# Flaps__2023-07-31.net
KiCad netlist of a schematic drawn in Altium Designer
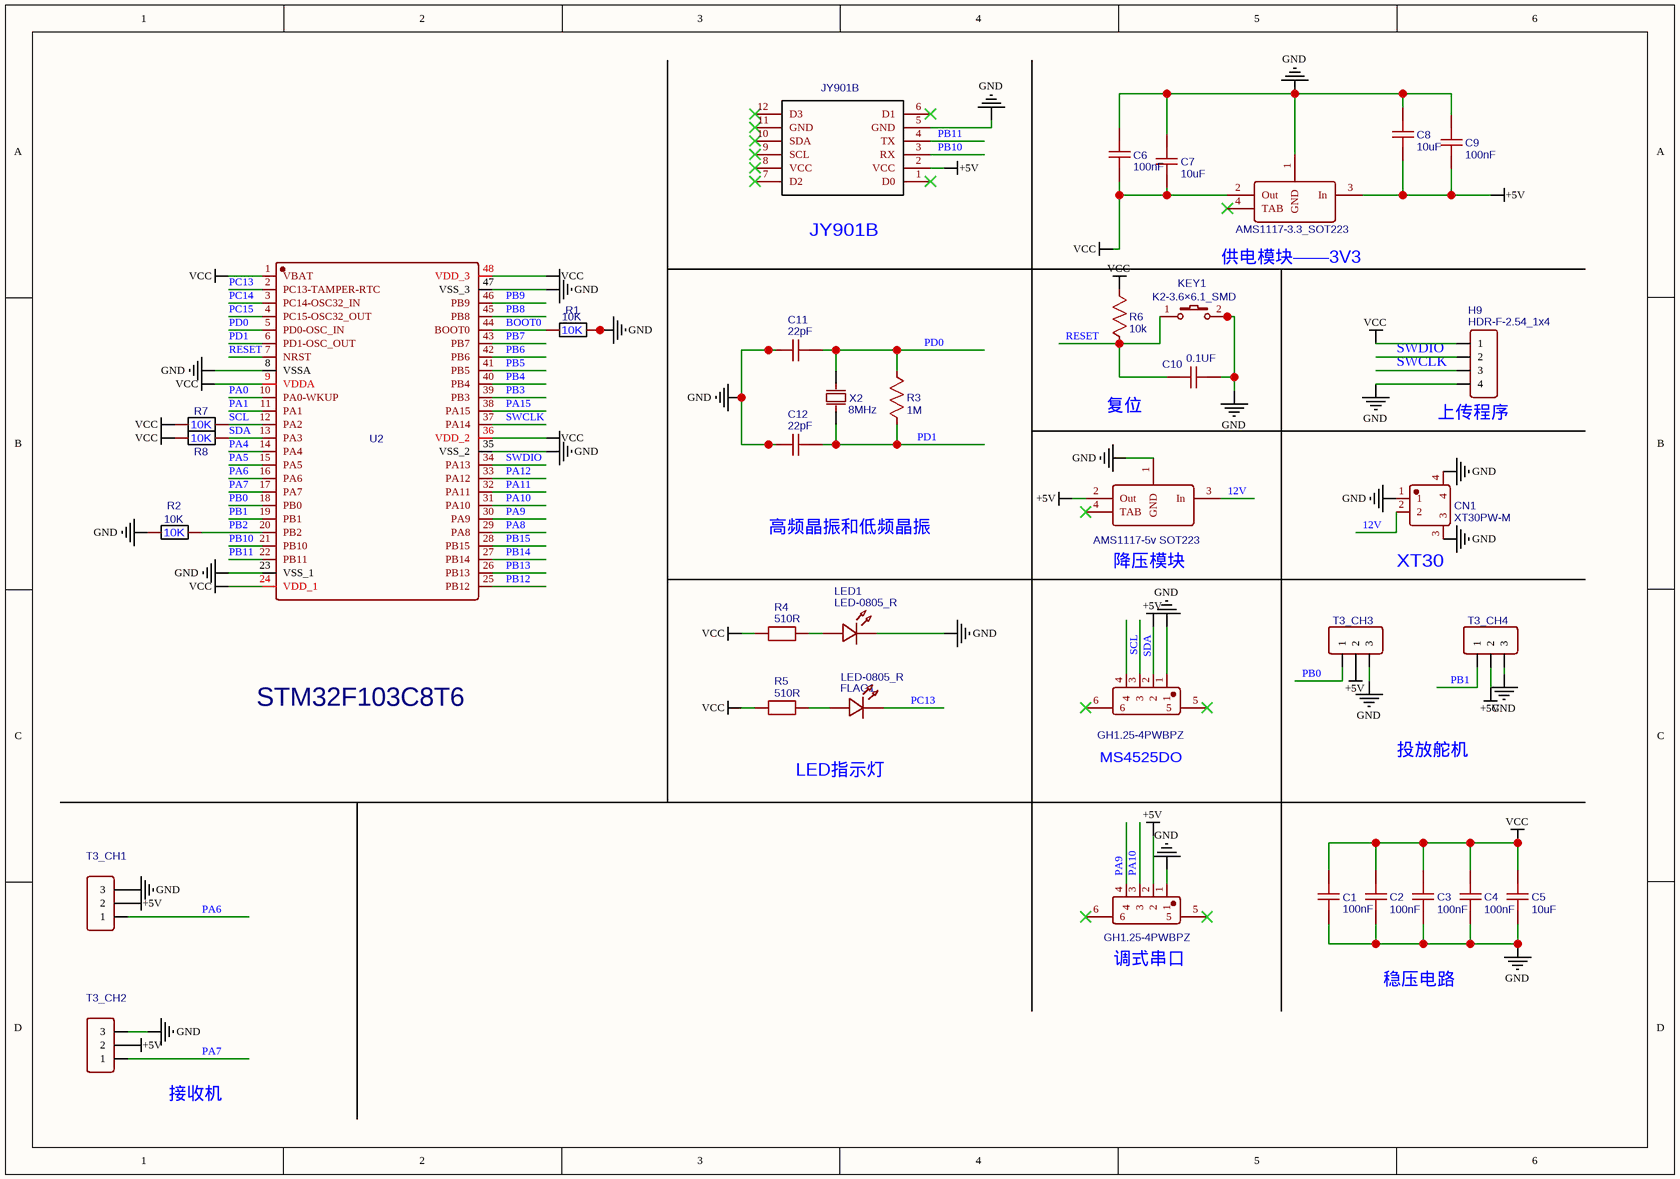
[diagram p0: Flaps第三版_2023-07-31.schdoc]

(export (version "E")
  (design (tool "Eeschema 10.0.6"))
  (components
    (comp (ref "C1")
      (value "100nF")
      (fields (field (name "CONTRIBUTOR") "LCEDA_Lib"))
      (libsource (lib "altium-import") (part "root_1_100nF_"))
    )
    (comp (ref "C2")
      (value "100nF")
      (fields (field (name "CONTRIBUTOR") "LCEDA_Lib"))
      (libsource (lib "altium-import") (part "root_1_100nF_"))
    )
    (comp (ref "C3")
      (value "100nF")
      (fields (field (name "CONTRIBUTOR") "LCEDA_Lib"))
      (libsource (lib "altium-import") (part "root_1_100nF_"))
    )
    (comp (ref "C4")
      (value "100nF")
      (fields (field (name "CONTRIBUTOR") "LCEDA_Lib"))
      (libsource (lib "altium-import") (part "root_1_100nF_"))
    )
    (comp (ref "C5")
      (value "10uF")
      (fields (field (name "CONTRIBUTOR") "LCEDA_Lib"))
      (libsource (lib "altium-import") (part "root_1_10uF_"))
    )
    (comp (ref "C6")
      (value "100nF")
      (fields (field (name "MANUFACTURER") "SAMSUNG") (field (name "MANUFACTURER PART") "CL10B104KC8NNNC"))
      (libsource (lib "altium-import") (part "root_3_100nF_"))
    )
    (comp (ref "C7")
      (value "10uF")
      (fields
        (field (name "MANUFACTURER") "Taiyo Yuden")
        (field (name "MANUFACTURER PART") "EMK316AB7106KL-T")
        (field (name "CONTRIBUTOR") "LCSC")
      )
      (libsource (lib "altium-import") (part "root_2_10uF_"))
    )
    (comp (ref "C8")
      (value "10uF")
      (fields
        (field (name "MANUFACTURER") "Taiyo Yuden")
        (field (name "MANUFACTURER PART") "EMK316AB7106KL-T")
        (field (name "CONTRIBUTOR") "LCSC")
      )
      (libsource (lib "altium-import") (part "root_2_10uF_"))
    )
    (comp (ref "C9")
      (value "100nF")
      (fields (field (name "MANUFACTURER") "SAMSUNG") (field (name "MANUFACTURER PART") "CL10B104KC8NNNC"))
      (libsource (lib "altium-import") (part "root_3_100nF_"))
    )
    (comp (ref "C10")
      (value "0.1UF")
      (fields (field (name "CONTRIBUTOR") "LCEDA_Lib"))
      (libsource (lib "altium-import") (part "root_0_0.1UF_"))
    )
    (comp (ref "C11")
      (value "22pF")
      (fields (field (name "CONTRIBUTOR") "LCEDA_Lib"))
      (libsource (lib "altium-import") (part "root_0_22pF_"))
    )
    (comp (ref "C12")
      (value "22pF")
      (fields (field (name "CONTRIBUTOR") "LCEDA_Lib"))
      (libsource (lib "altium-import") (part "root_0_22pF_"))
    )
    (comp (ref "CN1")
      (value "XT30PW-M")
      (fields (field (name "MANUFACTURER") "Changzhou Amass Elec") (field (name "CONTRIBUTOR") "LCSC"))
      (libsource (lib "altium-import") (part "root_0_XT30PW-M_"))
    )
    (comp (ref "FLAG1")
      (value "LED-0805_R")
      (fields
        (field (name "MANUFACTURER") "EVERLIGHT(台湾亿光)")
        (field (name "MANUFACTURER PART") "17-21SURC/S530-A3/TR8")
        (field (name "CONTRIBUTOR") "LCEDA_Lib")
      )
      (libsource (lib "altium-import") (part "root_0_LED-0805_R_"))
    )
    (comp (ref "H9")
      (value "HDR-F-2.54_1x4")
      (fields (field (name "CONTRIBUTOR") "LCEDA_Lib"))
      (libsource (lib "altium-import") (part "root_0_HDR-F-2.54_1x4_"))
    )
    (comp (ref "KEY1")
      (value "K2-3.6×6.1_SMD")
      (fields (field (name "MANUFACTURER PART") "K2-1107ST-A4SW-06") (field (name "CONTRIBUTOR") "LCEDA_Lib"))
      (libsource (lib "altium-import") (part "root_0_K2-3.6×6.1_SMD_"))
    )
    (comp (ref "LED1")
      (value "LED-0805_R")
      (fields
        (field (name "MANUFACTURER") "EVERLIGHT(台湾亿光)")
        (field (name "MANUFACTURER PART") "17-21SURC/S530-A3/TR8")
        (field (name "CONTRIBUTOR") "LCEDA_Lib")
      )
      (libsource (lib "altium-import") (part "root_0_LED-0805_R_"))
    )
    (comp (ref "R1")
      (value "10K")
      (fields (field (name "CONTRIBUTOR") "caocunzhangxiaobai"))
      (libsource (lib "altium-import") (part "root_0_10K_"))
    )
    (comp (ref "R2")
      (value "10K")
      (fields (field (name "CONTRIBUTOR") "caocunzhangxiaobai"))
      (libsource (lib "altium-import") (part "root_0_10K_"))
    )
    (comp (ref "R3")
      (value "1M")
      (fields (field (name "CONTRIBUTOR") "LCEDA_Lib"))
      (libsource (lib "altium-import") (part "root_1_1M_"))
    )
    (comp (ref "R4")
      (value "510R")
      (fields (field (name "CONTRIBUTOR") "LCEDA_Lib"))
      (libsource (lib "altium-import") (part "root_0_510R_"))
    )
    (comp (ref "R5")
      (value "510R")
      (fields (field (name "CONTRIBUTOR") "LCEDA_Lib"))
      (libsource (lib "altium-import") (part "root_0_510R_"))
    )
    (comp (ref "R6")
      (value "10k")
      (fields (field (name "CONTRIBUTOR") "LCEDA_Lib"))
      (libsource (lib "altium-import") (part "root_1_10k_"))
    )
    (comp (ref "R7")
      (value "10K")
      (fields (field (name "CONTRIBUTOR") "caocunzhangxiaobai"))
      (libsource (lib "altium-import") (part "root_0_10K_"))
    )
    (comp (ref "R8")
      (value "10K")
      (fields (field (name "CONTRIBUTOR") "caocunzhangxiaobai"))
      (libsource (lib "altium-import") (part "root_0_10K_"))
    )
    (comp (ref "T3_CH1")
      (value "HDR-F-2.54_1x3")
      (fields (field (name "CONTRIBUTOR") "LCEDA_Lib"))
      (libsource (lib "altium-import") (part "root_2_HDR-F-2.54_1x3_"))
    )
    (comp (ref "T3_CH2")
      (value "HDR-F-2.54_1x3")
      (fields (field (name "CONTRIBUTOR") "LCEDA_Lib"))
      (libsource (lib "altium-import") (part "root_2_HDR-F-2.54_1x3_"))
    )
    (comp (ref "T3_CH3")
      (value "HDR-F-2.54_1x3")
      (fields (field (name "CONTRIBUTOR") "LCEDA_Lib"))
      (libsource (lib "altium-import") (part "root_1_HDR-F-2.54_1x3_"))
    )
    (comp (ref "T3_CH4")
      (value "HDR-F-2.54_1x3")
      (fields (field (name "CONTRIBUTOR") "LCEDA_Lib"))
      (libsource (lib "altium-import") (part "root_1_HDR-F-2.54_1x3_"))
    )
    (comp (ref "U1")
      (value "AMS1117-3.3_SOT223")
      (fields
        (field (name "MANUFACTURER") "SK")
        (field (name "MANUFACTURER PART") "AMS1117-3.3")
        (field (name "CONTRIBUTOR") "LCSC")
      )
      (libsource (lib "altium-import") (part "root_2_AMS1117-3.3_SOT223_"))
    )
    (comp (ref "U2")
      (value "STM32F103C8T6")
      (fields (field (name "MANUFACTURER") "STMicroelectronics"))
      (libsource (lib "altium-import") (part "root_0_STM32F103C8T6_"))
    )
    (comp (ref "U3")
      (value "AMS1117-5v SOT223")
      (fields
        (field (name "MANUFACTURER") "SK")
        (field (name "MANUFACTURER PART") "AMS1117-3.3")
        (field (name "CONTRIBUTOR") "LCSC")
      )
      (libsource (lib "altium-import") (part "root_2_AMS1117-5v SOT223_"))
    )
    (comp (ref "U4")
      (value "GH1.25-4PWBPZ")
      (fields (field (name "MANUFACTURER") "BOOMELE(博穆精密)") (field (name "CONTRIBUTOR") "LCSC"))
      (libsource (lib "altium-import") (part "root_3_GH1.25-4PWBPZ_"))
    )
    (comp (ref "U5")
      (value "GH1.25-4PWBPZ")
      (fields (field (name "MANUFACTURER") "BOOMELE(博穆精密)") (field (name "CONTRIBUTOR") "LCSC"))
      (libsource (lib "altium-import") (part "root_3_GH1.25-4PWBPZ_"))
    )
    (comp (ref "U9")
      (value "JY901B")
      (fields (field (name "CONTRIBUTOR") "230W"))
      (libsource (lib "altium-import") (part "root_2_JY901B_"))
    )
    (comp (ref "X2")
      (value "8MHz")
      (fields (field (name "MANUFACTURER") "HOSONIC") (field (name "MANUFACTURER PART") "ESB8.00000F20E22"))
      (libsource (lib "altium-import") (part "root_1_8MHz_"))
    )
  )
  (nets
    (net (code "1") (name "+5V") (class "Default")
      (node (ref "C8") (pin "2") (pinfunction "2_2") (pintype "passive"))
      (node (ref "C9") (pin "2") (pinfunction "2_2") (pintype "passive"))
      (node (ref "T3_CH1") (pin "2") (pinfunction "2_2") (pintype "passive"))
      (node (ref "T3_CH2") (pin "2") (pinfunction "2_2") (pintype "passive"))
      (node (ref "T3_CH3") (pin "2") (pinfunction "2_2") (pintype "passive"))
      (node (ref "T3_CH4") (pin "2") (pinfunction "2_2") (pintype "passive"))
      (node (ref "U1") (pin "3") (pinfunction "In_3") (pintype "passive"))
      (node (ref "U3") (pin "2") (pinfunction "Out_2") (pintype "passive"))
      (node (ref "U4") (pin "2") (pinfunction "2_2") (pintype "passive"))
      (node (ref "U5") (pin "2") (pinfunction "2_2") (pintype "passive"))
      (node (ref "U9") (pin "2") (pinfunction "VCC_2") (pintype "passive"))
    )
    (net (code "2") (name "/12V") (class "Default")
      (node (ref "CN1") (pin "2") (pinfunction "2_2") (pintype "passive"))
      (node (ref "U3") (pin "3") (pinfunction "In_3") (pintype "passive"))
    )
    (net (code "3") (name "/BOOT0") (class "Default")
      (node (ref "R1") (pin "1") (pinfunction "1_1") (pintype "passive"))
      (node (ref "U2") (pin "44") (pinfunction "BOOT0_44") (pintype "passive"))
    )
    (net (code "4") (name "/PA0") (class "Default")
      (node (ref "U2") (pin "10") (pinfunction "PA0-WKUP_10") (pintype "passive"))
    )
    (net (code "5") (name "/PA1") (class "Default")
      (node (ref "U2") (pin "11") (pinfunction "PA1_11") (pintype "passive"))
    )
    (net (code "6") (name "/PA4") (class "Default")
      (node (ref "U2") (pin "14") (pinfunction "PA4_14") (pintype "passive"))
    )
    (net (code "7") (name "/PA5") (class "Default")
      (node (ref "U2") (pin "15") (pinfunction "PA5_15") (pintype "passive"))
    )
    (net (code "8") (name "/PA6") (class "Default")
      (node (ref "T3_CH1") (pin "1") (pinfunction "1_1") (pintype "passive"))
      (node (ref "U2") (pin "16") (pinfunction "PA6_16") (pintype "passive"))
    )
    (net (code "9") (name "/PA7") (class "Default")
      (node (ref "T3_CH2") (pin "1") (pinfunction "1_1") (pintype "passive"))
      (node (ref "U2") (pin "17") (pinfunction "PA7_17") (pintype "passive"))
    )
    (net (code "10") (name "/PA8") (class "Default")
      (node (ref "U2") (pin "29") (pinfunction "PA8_29") (pintype "passive"))
    )
    (net (code "11") (name "/PA9") (class "Default")
      (node (ref "U2") (pin "30") (pinfunction "PA9_30") (pintype "passive"))
      (node (ref "U5") (pin "4") (pinfunction "4_4") (pintype "passive"))
    )
    (net (code "12") (name "/PA10") (class "Default")
      (node (ref "U2") (pin "31") (pinfunction "PA10_31") (pintype "passive"))
      (node (ref "U5") (pin "3") (pinfunction "3_3") (pintype "passive"))
    )
    (net (code "13") (name "/PA11") (class "Default")
      (node (ref "U2") (pin "32") (pinfunction "PA11_32") (pintype "passive"))
    )
    (net (code "14") (name "/PA12") (class "Default")
      (node (ref "U2") (pin "33") (pinfunction "PA12_33") (pintype "passive"))
    )
    (net (code "15") (name "/PA15") (class "Default")
      (node (ref "U2") (pin "38") (pinfunction "PA15_38") (pintype "passive"))
    )
    (net (code "16") (name "/PB0") (class "Default")
      (node (ref "T3_CH3") (pin "1") (pinfunction "1_1") (pintype "passive"))
      (node (ref "U2") (pin "18") (pinfunction "PB0_18") (pintype "passive"))
    )
    (net (code "17") (name "/PB1") (class "Default")
      (node (ref "T3_CH4") (pin "1") (pinfunction "1_1") (pintype "passive"))
      (node (ref "U2") (pin "19") (pinfunction "PB1_19") (pintype "passive"))
    )
    (net (code "18") (name "/PB2") (class "Default")
      (node (ref "R2") (pin "2") (pinfunction "2_2") (pintype "passive"))
      (node (ref "U2") (pin "20") (pinfunction "PB2_20") (pintype "passive"))
    )
    (net (code "19") (name "/PB3") (class "Default")
      (node (ref "U2") (pin "39") (pinfunction "PB3_39") (pintype "passive"))
    )
    (net (code "20") (name "/PB4") (class "Default")
      (node (ref "U2") (pin "40") (pinfunction "PB4_40") (pintype "passive"))
    )
    (net (code "21") (name "/PB5") (class "Default")
      (node (ref "U2") (pin "41") (pinfunction "PB5_41") (pintype "passive"))
    )
    (net (code "22") (name "/PB6") (class "Default")
      (node (ref "U2") (pin "42") (pinfunction "PB6_42") (pintype "passive"))
    )
    (net (code "23") (name "/PB7") (class "Default")
      (node (ref "U2") (pin "43") (pinfunction "PB7_43") (pintype "passive"))
    )
    (net (code "24") (name "/PB8") (class "Default")
      (node (ref "U2") (pin "45") (pinfunction "PB8_45") (pintype "passive"))
    )
    (net (code "25") (name "/PB9") (class "Default")
      (node (ref "U2") (pin "46") (pinfunction "PB9_46") (pintype "passive"))
    )
    (net (code "26") (name "/PB10") (class "Default")
      (node (ref "U2") (pin "21") (pinfunction "PB10_21") (pintype "passive"))
      (node (ref "U9") (pin "3") (pinfunction "RX_3") (pintype "passive"))
    )
    (net (code "27") (name "/PB11") (class "Default")
      (node (ref "U2") (pin "22") (pinfunction "PB11_22") (pintype "passive"))
      (node (ref "U9") (pin "4") (pinfunction "TX_4") (pintype "passive"))
    )
    (net (code "28") (name "/PB12") (class "Default")
      (node (ref "U2") (pin "25") (pinfunction "PB12_25") (pintype "passive"))
    )
    (net (code "29") (name "/PB13") (class "Default")
      (node (ref "U2") (pin "26") (pinfunction "PB13_26") (pintype "passive"))
    )
    (net (code "30") (name "/PB14") (class "Default")
      (node (ref "U2") (pin "27") (pinfunction "PB14_27") (pintype "passive"))
    )
    (net (code "31") (name "/PB15") (class "Default")
      (node (ref "U2") (pin "28") (pinfunction "PB15_28") (pintype "passive"))
    )
    (net (code "32") (name "/PC13") (class "Default")
      (node (ref "FLAG1") (pin "2") (pinfunction "2_2") (pintype "passive"))
      (node (ref "U2") (pin "2") (pinfunction "PC13-TAMPER-RTC_2") (pintype "passive"))
    )
    (net (code "33") (name "/PC14") (class "Default")
      (node (ref "U2") (pin "3") (pinfunction "PC14-OSC32_IN_3") (pintype "passive"))
    )
    (net (code "34") (name "/PC15") (class "Default")
      (node (ref "U2") (pin "4") (pinfunction "PC15-OSC32_OUT_4") (pintype "passive"))
    )
    (net (code "35") (name "/PD0") (class "Default")
      (node (ref "C11") (pin "2") (pinfunction "2_2") (pintype "passive"))
      (node (ref "R3") (pin "2") (pinfunction "2_2") (pintype "passive"))
      (node (ref "U2") (pin "5") (pinfunction "PD0-OSC_IN_5") (pintype "passive"))
      (node (ref "X2") (pin "2") (pinfunction "OSC2_2") (pintype "passive"))
    )
    (net (code "36") (name "/PD1") (class "Default")
      (node (ref "C12") (pin "2") (pinfunction "2_2") (pintype "passive"))
      (node (ref "R3") (pin "1") (pinfunction "1_1") (pintype "passive"))
      (node (ref "U2") (pin "6") (pinfunction "PD1-OSC_OUT_6") (pintype "passive"))
      (node (ref "X2") (pin "1") (pinfunction "OSC1_1") (pintype "passive"))
    )
    (net (code "37") (name "/RESET") (class "Default")
      (node (ref "C10") (pin "1") (pinfunction "1_1") (pintype "passive"))
      (node (ref "KEY1") (pin "1") (pinfunction "1_1") (pintype "passive"))
      (node (ref "R6") (pin "1") (pinfunction "1_1") (pintype "passive"))
      (node (ref "U2") (pin "7") (pinfunction "NRST_7") (pintype "passive"))
    )
    (net (code "38") (name "/SCL") (class "Default")
      (node (ref "R7") (pin "2") (pinfunction "2_2") (pintype "passive"))
      (node (ref "U2") (pin "12") (pinfunction "PA2_12") (pintype "passive"))
      (node (ref "U4") (pin "4") (pinfunction "4_4") (pintype "passive"))
    )
    (net (code "39") (name "/SDA") (class "Default")
      (node (ref "R8") (pin "2") (pinfunction "2_2") (pintype "passive"))
      (node (ref "U2") (pin "13") (pinfunction "PA3_13") (pintype "passive"))
      (node (ref "U4") (pin "3") (pinfunction "3_3") (pintype "passive"))
    )
    (net (code "40") (name "/SWCLK") (class "Default")
      (node (ref "H9") (pin "3") (pinfunction "3_3") (pintype "passive"))
      (node (ref "U2") (pin "37") (pinfunction "PA14_37") (pintype "passive"))
    )
    (net (code "41") (name "/SWDIO") (class "Default")
      (node (ref "H9") (pin "2") (pinfunction "2_2") (pintype "passive"))
      (node (ref "U2") (pin "34") (pinfunction "PA13_34") (pintype "passive"))
    )
    (net (code "42") (name "GND") (class "Default")
      (node (ref "C1") (pin "1") (pinfunction "1_1") (pintype "passive"))
      (node (ref "C10") (pin "2") (pinfunction "2_2") (pintype "passive"))
      (node (ref "C11") (pin "1") (pinfunction "1_1") (pintype "passive"))
      (node (ref "C12") (pin "1") (pinfunction "1_1") (pintype "passive"))
      (node (ref "C2") (pin "1") (pinfunction "1_1") (pintype "passive"))
      (node (ref "C3") (pin "1") (pinfunction "1_1") (pintype "passive"))
      (node (ref "C4") (pin "1") (pinfunction "1_1") (pintype "passive"))
      (node (ref "C5") (pin "1") (pinfunction "1_1") (pintype "passive"))
      (node (ref "C6") (pin "1") (pinfunction "1_1") (pintype "passive"))
      (node (ref "C7") (pin "1") (pinfunction "1_1") (pintype "passive"))
      (node (ref "C8") (pin "1") (pinfunction "1_1") (pintype "passive"))
      (node (ref "C9") (pin "1") (pinfunction "1_1") (pintype "passive"))
      (node (ref "CN1") (pin "1") (pinfunction "1_1") (pintype "passive"))
      (node (ref "CN1") (pin "3") (pinfunction "3_3") (pintype "passive"))
      (node (ref "CN1") (pin "4") (pinfunction "4_4") (pintype "passive"))
      (node (ref "H9") (pin "4") (pinfunction "4_4") (pintype "passive"))
      (node (ref "KEY1") (pin "2") (pinfunction "2_2") (pintype "passive"))
      (node (ref "LED1") (pin "2") (pinfunction "2_2") (pintype "passive"))
      (node (ref "R1") (pin "2") (pinfunction "2_2") (pintype "passive"))
      (node (ref "R2") (pin "1") (pinfunction "1_1") (pintype "passive"))
      (node (ref "T3_CH1") (pin "3") (pinfunction "3_3") (pintype "passive"))
      (node (ref "T3_CH2") (pin "3") (pinfunction "3_3") (pintype "passive"))
      (node (ref "T3_CH3") (pin "3") (pinfunction "3_3") (pintype "passive"))
      (node (ref "T3_CH4") (pin "3") (pinfunction "3_3") (pintype "passive"))
      (node (ref "U1") (pin "1") (pinfunction "GND_1") (pintype "passive"))
      (node (ref "U2") (pin "23") (pinfunction "VSS_1_23") (pintype "passive"))
      (node (ref "U2") (pin "35") (pinfunction "VSS_2_35") (pintype "passive"))
      (node (ref "U2") (pin "47") (pinfunction "VSS_3_47") (pintype "passive"))
      (node (ref "U2") (pin "8") (pinfunction "VSSA_8") (pintype "passive"))
      (node (ref "U3") (pin "1") (pinfunction "GND_1") (pintype "passive"))
      (node (ref "U4") (pin "1") (pinfunction "1_1") (pintype "passive"))
      (node (ref "U5") (pin "1") (pinfunction "1_1") (pintype "passive"))
      (node (ref "U9") (pin "5") (pinfunction "GND_5") (pintype "passive"))
    )
    (net (code "43") (name "Net-(FLAG1-Pad1)") (class "Default")
      (node (ref "FLAG1") (pin "1") (pinfunction "1_1") (pintype "passive"))
      (node (ref "R5") (pin "2") (pinfunction "2_2") (pintype "passive"))
    )
    (net (code "44") (name "Net-(LED1-Pad1)") (class "Default")
      (node (ref "LED1") (pin "1") (pinfunction "1_1") (pintype "passive"))
      (node (ref "R4") (pin "2") (pinfunction "2_2") (pintype "passive"))
    )
    (net (code "45") (name "VCC") (class "Default")
      (node (ref "C1") (pin "2") (pinfunction "2_2") (pintype "passive"))
      (node (ref "C2") (pin "2") (pinfunction "2_2") (pintype "passive"))
      (node (ref "C3") (pin "2") (pinfunction "2_2") (pintype "passive"))
      (node (ref "C4") (pin "2") (pinfunction "2_2") (pintype "passive"))
      (node (ref "C5") (pin "2") (pinfunction "2_2") (pintype "passive"))
      (node (ref "C6") (pin "2") (pinfunction "2_2") (pintype "passive"))
      (node (ref "C7") (pin "2") (pinfunction "2_2") (pintype "passive"))
      (node (ref "H9") (pin "1") (pinfunction "1_1") (pintype "passive"))
      (node (ref "R4") (pin "1") (pinfunction "1_1") (pintype "passive"))
      (node (ref "R5") (pin "1") (pinfunction "1_1") (pintype "passive"))
      (node (ref "R6") (pin "2") (pinfunction "2_2") (pintype "passive"))
      (node (ref "R7") (pin "1") (pinfunction "1_1") (pintype "passive"))
      (node (ref "R8") (pin "1") (pinfunction "1_1") (pintype "passive"))
      (node (ref "U1") (pin "2") (pinfunction "Out_2") (pintype "passive"))
      (node (ref "U2") (pin "1") (pinfunction "VBAT_1") (pintype "passive"))
      (node (ref "U2") (pin "24") (pinfunction "VDD_1_24") (pintype "passive"))
      (node (ref "U2") (pin "36") (pinfunction "VDD_2_36") (pintype "passive"))
      (node (ref "U2") (pin "48") (pinfunction "VDD_3_48") (pintype "passive"))
      (node (ref "U2") (pin "9") (pinfunction "VDDA_9") (pintype "passive"))
    )
    (net (code "46") (name "unconnected-(U1-TAB-Pad4)") (class "Default")
      (node (ref "U1") (pin "4") (pinfunction "TAB_4") (pintype "passive+no_connect"))
    )
    (net (code "47") (name "unconnected-(U3-TAB-Pad4)") (class "Default")
      (node (ref "U3") (pin "4") (pinfunction "TAB_4") (pintype "passive+no_connect"))
    )
    (net (code "48") (name "unconnected-(U4-Pad5)") (class "Default")
      (node (ref "U4") (pin "5") (pinfunction "5_5") (pintype "passive+no_connect"))
    )
    (net (code "49") (name "unconnected-(U4-Pad6)") (class "Default")
      (node (ref "U4") (pin "6") (pinfunction "6_6") (pintype "passive+no_connect"))
    )
    (net (code "50") (name "unconnected-(U5-Pad5)") (class "Default")
      (node (ref "U5") (pin "5") (pinfunction "5_5") (pintype "passive+no_connect"))
    )
    (net (code "51") (name "unconnected-(U5-Pad6)") (class "Default")
      (node (ref "U5") (pin "6") (pinfunction "6_6") (pintype "passive+no_connect"))
    )
    (net (code "52") (name "unconnected-(U9-D0-Pad1)") (class "Default")
      (node (ref "U9") (pin "1") (pinfunction "D0_1") (pintype "passive+no_connect"))
    )
    (net (code "53") (name "unconnected-(U9-D1-Pad6)") (class "Default")
      (node (ref "U9") (pin "6") (pinfunction "D1_6") (pintype "passive+no_connect"))
    )
    (net (code "54") (name "unconnected-(U9-D2-Pad7)") (class "Default")
      (node (ref "U9") (pin "7") (pinfunction "D2_7") (pintype "passive+no_connect"))
    )
    (net (code "55") (name "unconnected-(U9-D3-Pad12)") (class "Default")
      (node (ref "U9") (pin "12") (pinfunction "D3_12") (pintype "passive+no_connect"))
    )
    (net (code "56") (name "unconnected-(U9-GND-Pad11)") (class "Default")
      (node (ref "U9") (pin "11") (pinfunction "GND_11") (pintype "passive+no_connect"))
    )
    (net (code "57") (name "unconnected-(U9-SCL-Pad9)") (class "Default")
      (node (ref "U9") (pin "9") (pinfunction "SCL_9") (pintype "passive+no_connect"))
    )
    (net (code "58") (name "unconnected-(U9-SDA-Pad10)") (class "Default")
      (node (ref "U9") (pin "10") (pinfunction "SDA_10") (pintype "passive+no_connect"))
    )
    (net (code "59") (name "unconnected-(U9-VCC-Pad8)") (class "Default")
      (node (ref "U9") (pin "8") (pinfunction "VCC_8") (pintype "passive+no_connect"))
    )
  )
)
